# DL380P_r1_Fan_Control.net
KiCad netlist of a schematic drawn in EAGLE
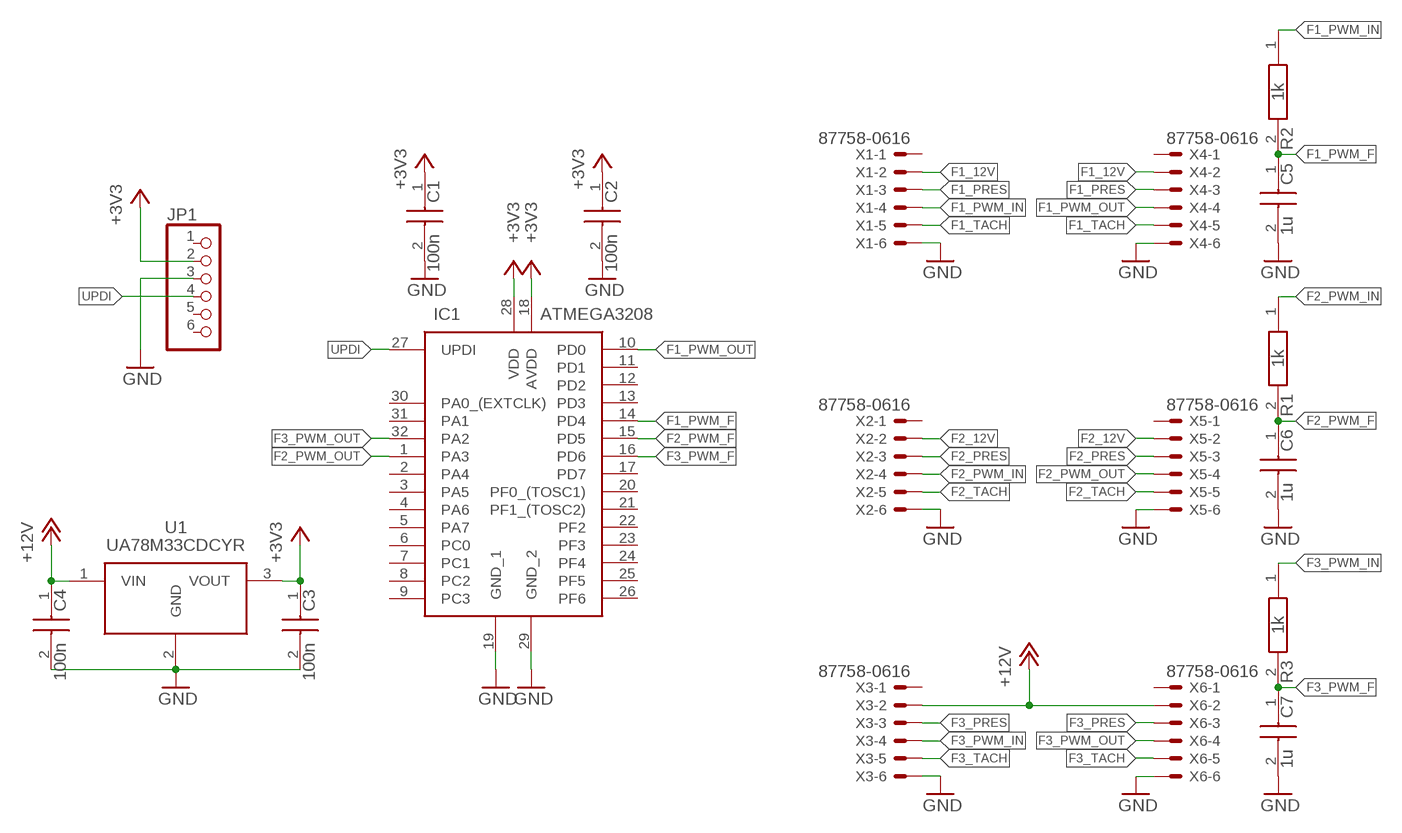
[diagram p0: schematic, sheet 1]

(export (version "E")
  (design (tool "Eeschema 10.0.6"))
  (components
    (comp (ref "C1")
      (value "100n")
      (footprint "eagle-import:CAPC1608X90N")
      (fields
        (field (name "MANUFACTURER_PART_NUMBER") "06033C104KAT2A")
        (field (name "MOUSER_PART_NUMBER") "581-06033C104KAT2A")
      )
      (libsource (lib "eagle-import") (part "_CAP_0603_100N_25V_10%_(X7R)"))
    )
    (comp (ref "C2")
      (value "100n")
      (footprint "eagle-import:CAPC1608X90N")
      (fields
        (field (name "MANUFACTURER_PART_NUMBER") "06033C104KAT2A")
        (field (name "MOUSER_PART_NUMBER") "581-06033C104KAT2A")
      )
      (libsource (lib "eagle-import") (part "_CAP_0603_100N_25V_10%_(X7R)"))
    )
    (comp (ref "C3")
      (value "100n")
      (footprint "eagle-import:CAPC1608X90N")
      (fields
        (field (name "MANUFACTURER_PART_NUMBER") "06033C104KAT2A")
        (field (name "MOUSER_PART_NUMBER") "581-06033C104KAT2A")
      )
      (libsource (lib "eagle-import") (part "_CAP_0603_100N_25V_10%_(X7R)"))
    )
    (comp (ref "C4")
      (value "100n")
      (footprint "eagle-import:CAPC1608X90N")
      (fields
        (field (name "MANUFACTURER_PART_NUMBER") "06033C104KAT2A")
        (field (name "MOUSER_PART_NUMBER") "581-06033C104KAT2A")
      )
      (libsource (lib "eagle-import") (part "_CAP_0603_100N_25V_10%_(X7R)"))
    )
    (comp (ref "C5")
      (value "1u")
      (footprint "eagle-import:CAPC1608X90N")
      (fields
        (field (name "MANUFACTURER_PART_NUMBER") "06033C105KAT2A")
        (field (name "MOUSER_PART_NUMBER") "581-06033C105KAT2A")
      )
      (libsource (lib "eagle-import") (part "_CAP_0603_1U_25V_10%_(X7R)"))
    )
    (comp (ref "C6")
      (value "1u")
      (footprint "eagle-import:CAPC1608X90N")
      (fields
        (field (name "MANUFACTURER_PART_NUMBER") "06033C105KAT2A")
        (field (name "MOUSER_PART_NUMBER") "581-06033C105KAT2A")
      )
      (libsource (lib "eagle-import") (part "_CAP_0603_1U_25V_10%_(X7R)"))
    )
    (comp (ref "C7")
      (value "1u")
      (footprint "eagle-import:CAPC1608X90N")
      (fields
        (field (name "MANUFACTURER_PART_NUMBER") "06033C105KAT2A")
        (field (name "MOUSER_PART_NUMBER") "581-06033C105KAT2A")
      )
      (libsource (lib "eagle-import") (part "_CAP_0603_1U_25V_10%_(X7R)"))
    )
    (comp (ref "IC1")
      (value "ATMEGA3208")
      (footprint "eagle-import:QFP80P900X900X120-32N")
      (fields
        (field (name "MANUFACTURER_PART_NUMBER") "ATMEGA3208-AFR")
        (field (name "MOUSER_PART_NUMBER") "579-ATMEGA3208AFR")
      )
      (libsource (lib "eagle-import") (part "_UC_ATMEGA3208-TQFP-32"))
    )
    (comp (ref "JP1")
      (value "PINHD-1X6LOCK")
      (footprint "eagle-import:1X06-BIGLOCK")
      (libsource (lib "eagle-import") (part "PINHD-1X6LOCK"))
    )
    (comp (ref "R1")
      (value "1k")
      (footprint "eagle-import:RESC1608X55N")
      (fields
        (field (name "MANUFACTURER_PART_NUMBER") "RK73H1JTTDD1001F")
        (field (name "MOUSER_PART_NUMBER") "660-RK73H1JTTDD1001F")
      )
      (libsource (lib "eagle-import") (part "_RES_0603_1K_1/10W_1%_(RK73H1JTTD)"))
    )
    (comp (ref "R2")
      (value "1k")
      (footprint "eagle-import:RESC1608X55N")
      (fields
        (field (name "MANUFACTURER_PART_NUMBER") "RK73H1JTTDD1001F")
        (field (name "MOUSER_PART_NUMBER") "660-RK73H1JTTDD1001F")
      )
      (libsource (lib "eagle-import") (part "_RES_0603_1K_1/10W_1%_(RK73H1JTTD)"))
    )
    (comp (ref "R3")
      (value "1k")
      (footprint "eagle-import:RESC1608X55N")
      (fields
        (field (name "MANUFACTURER_PART_NUMBER") "RK73H1JTTDD1001F")
        (field (name "MOUSER_PART_NUMBER") "660-RK73H1JTTDD1001F")
      )
      (libsource (lib "eagle-import") (part "_RES_0603_1K_1/10W_1%_(RK73H1JTTD)"))
    )
    (comp (ref "U1")
      (value "UA78M33CDCYR")
      (footprint "eagle-import:SOT230P700X180-4N")
      (fields (field (name "MOUSER_PART_NUMBER") "595-UA78M33CDCYR"))
      (libsource (lib "eagle-import") (part "_REG_3.3V_0.5A_SOT-223_(5.3-25V)_(UA78M33CDCYR)"))
    )
    (comp (ref "X1")
      (value "87758-0616")
      (footprint "eagle-import:87758-0616")
      (fields (field (name "MF") "MOLEX"))
      (libsource (lib "eagle-import") (part "87758-0616"))
    )
    (comp (ref "X2")
      (value "87758-0616")
      (footprint "eagle-import:87758-0616")
      (fields (field (name "MF") "MOLEX"))
      (libsource (lib "eagle-import") (part "87758-0616"))
    )
    (comp (ref "X3")
      (value "87758-0616")
      (footprint "eagle-import:87758-0616")
      (fields (field (name "MF") "MOLEX"))
      (libsource (lib "eagle-import") (part "87758-0616"))
    )
    (comp (ref "X4")
      (value "87758-0616")
      (footprint "eagle-import:87758-0616")
      (fields (field (name "MF") "MOLEX"))
      (libsource (lib "eagle-import") (part "87758-0616"))
    )
    (comp (ref "X5")
      (value "87758-0616")
      (footprint "eagle-import:87758-0616")
      (fields (field (name "MF") "MOLEX"))
      (libsource (lib "eagle-import") (part "87758-0616"))
    )
    (comp (ref "X6")
      (value "87758-0616")
      (footprint "eagle-import:87758-0616")
      (fields (field (name "MF") "MOLEX"))
      (libsource (lib "eagle-import") (part "87758-0616"))
    )
  )
  (nets
    (net (code "1") (name "+3V3") (class "Default")
      (node (ref "C1") (pin "1") (pinfunction "1_1") (pintype "bidirectional"))
      (node (ref "C2") (pin "1") (pinfunction "1_1") (pintype "bidirectional"))
      (node (ref "C3") (pin "1") (pinfunction "1_1") (pintype "bidirectional"))
      (node (ref "IC1") (pin "18") (pinfunction "AVDD_18") (pintype "bidirectional"))
      (node (ref "IC1") (pin "28") (pinfunction "VDD_28") (pintype "bidirectional"))
      (node (ref "JP1") (pin "2") (pinfunction "2_2") (pintype "passive"))
      (node (ref "U1") (pin "3") (pinfunction "VOUT_3") (pintype "bidirectional"))
    )
    (net (code "2") (name "+12V") (class "Default")
      (node (ref "C4") (pin "1") (pinfunction "1_1") (pintype "bidirectional"))
      (node (ref "U1") (pin "1") (pinfunction "VIN_1") (pintype "bidirectional"))
      (node (ref "X3") (pin "2") (pinfunction "S_2") (pintype "passive"))
      (node (ref "X6") (pin "2") (pinfunction "S_2") (pintype "passive"))
    )
    (net (code "3") (name "F1_12V") (class "Default")
      (node (ref "X1") (pin "2") (pinfunction "S_2") (pintype "passive"))
      (node (ref "X4") (pin "2") (pinfunction "S_2") (pintype "passive"))
    )
    (net (code "4") (name "F1_PRES") (class "Default")
      (node (ref "X1") (pin "3") (pinfunction "S_3") (pintype "passive"))
      (node (ref "X4") (pin "3") (pinfunction "S_3") (pintype "passive"))
    )
    (net (code "5") (name "F1_PWM_F") (class "Default")
      (node (ref "C5") (pin "1") (pinfunction "1_1") (pintype "bidirectional"))
      (node (ref "IC1") (pin "14") (pinfunction "PD4_14") (pintype "bidirectional"))
      (node (ref "R2") (pin "2") (pinfunction "2_2") (pintype "bidirectional"))
    )
    (net (code "6") (name "F1_PWM_IN") (class "Default")
      (node (ref "R2") (pin "1") (pinfunction "1_1") (pintype "bidirectional"))
      (node (ref "X1") (pin "4") (pinfunction "S_4") (pintype "passive"))
    )
    (net (code "7") (name "F1_PWM_OUT") (class "Default")
      (node (ref "IC1") (pin "10") (pinfunction "PD0_10") (pintype "bidirectional"))
      (node (ref "X4") (pin "4") (pinfunction "S_4") (pintype "passive"))
    )
    (net (code "8") (name "F1_TACH") (class "Default")
      (node (ref "X1") (pin "5") (pinfunction "S_5") (pintype "passive"))
      (node (ref "X4") (pin "5") (pinfunction "S_5") (pintype "passive"))
    )
    (net (code "9") (name "F2_12V") (class "Default")
      (node (ref "X2") (pin "2") (pinfunction "S_2") (pintype "passive"))
      (node (ref "X5") (pin "2") (pinfunction "S_2") (pintype "passive"))
    )
    (net (code "10") (name "F2_PRES") (class "Default")
      (node (ref "X2") (pin "3") (pinfunction "S_3") (pintype "passive"))
      (node (ref "X5") (pin "3") (pinfunction "S_3") (pintype "passive"))
    )
    (net (code "11") (name "F2_PWM_F") (class "Default")
      (node (ref "C6") (pin "1") (pinfunction "1_1") (pintype "bidirectional"))
      (node (ref "IC1") (pin "15") (pinfunction "PD5_15") (pintype "bidirectional"))
      (node (ref "R1") (pin "2") (pinfunction "2_2") (pintype "bidirectional"))
    )
    (net (code "12") (name "F2_PWM_IN") (class "Default")
      (node (ref "R1") (pin "1") (pinfunction "1_1") (pintype "bidirectional"))
      (node (ref "X2") (pin "4") (pinfunction "S_4") (pintype "passive"))
    )
    (net (code "13") (name "F2_PWM_OUT") (class "Default")
      (node (ref "IC1") (pin "1") (pinfunction "PA3_1") (pintype "bidirectional"))
      (node (ref "X5") (pin "4") (pinfunction "S_4") (pintype "passive"))
    )
    (net (code "14") (name "F2_TACH") (class "Default")
      (node (ref "X2") (pin "5") (pinfunction "S_5") (pintype "passive"))
      (node (ref "X5") (pin "5") (pinfunction "S_5") (pintype "passive"))
    )
    (net (code "15") (name "F3_PRES") (class "Default")
      (node (ref "X3") (pin "3") (pinfunction "S_3") (pintype "passive"))
      (node (ref "X6") (pin "3") (pinfunction "S_3") (pintype "passive"))
    )
    (net (code "16") (name "F3_PWM_F") (class "Default")
      (node (ref "C7") (pin "1") (pinfunction "1_1") (pintype "bidirectional"))
      (node (ref "IC1") (pin "16") (pinfunction "PD6_16") (pintype "bidirectional"))
      (node (ref "R3") (pin "2") (pinfunction "2_2") (pintype "bidirectional"))
    )
    (net (code "17") (name "F3_PWM_IN") (class "Default")
      (node (ref "R3") (pin "1") (pinfunction "1_1") (pintype "bidirectional"))
      (node (ref "X3") (pin "4") (pinfunction "S_4") (pintype "passive"))
    )
    (net (code "18") (name "F3_PWM_OUT") (class "Default")
      (node (ref "IC1") (pin "32") (pinfunction "PA2_32") (pintype "bidirectional"))
      (node (ref "X6") (pin "4") (pinfunction "S_4") (pintype "passive"))
    )
    (net (code "19") (name "F3_TACH") (class "Default")
      (node (ref "X3") (pin "5") (pinfunction "S_5") (pintype "passive"))
      (node (ref "X6") (pin "5") (pinfunction "S_5") (pintype "passive"))
    )
    (net (code "20") (name "GND") (class "Default")
      (node (ref "C1") (pin "2") (pinfunction "2_2") (pintype "bidirectional"))
      (node (ref "C2") (pin "2") (pinfunction "2_2") (pintype "bidirectional"))
      (node (ref "C3") (pin "2") (pinfunction "2_2") (pintype "bidirectional"))
      (node (ref "C4") (pin "2") (pinfunction "2_2") (pintype "bidirectional"))
      (node (ref "C5") (pin "2") (pinfunction "2_2") (pintype "bidirectional"))
      (node (ref "C6") (pin "2") (pinfunction "2_2") (pintype "bidirectional"))
      (node (ref "C7") (pin "2") (pinfunction "2_2") (pintype "bidirectional"))
      (node (ref "IC1") (pin "19") (pinfunction "GND_1_19") (pintype "bidirectional"))
      (node (ref "IC1") (pin "29") (pinfunction "GND_2_29") (pintype "bidirectional"))
      (node (ref "JP1") (pin "3") (pinfunction "3_3") (pintype "passive"))
      (node (ref "U1") (pin "2") (pinfunction "GND_2") (pintype "bidirectional"))
      (node (ref "U1") (pin "4") (pinfunction "GND_1_4") (pintype "bidirectional"))
      (node (ref "X1") (pin "6") (pinfunction "S_6") (pintype "passive"))
      (node (ref "X2") (pin "6") (pinfunction "S_6") (pintype "passive"))
      (node (ref "X3") (pin "6") (pinfunction "S_6") (pintype "passive"))
      (node (ref "X4") (pin "6") (pinfunction "S_6") (pintype "passive"))
      (node (ref "X5") (pin "6") (pinfunction "S_6") (pintype "passive"))
      (node (ref "X6") (pin "6") (pinfunction "S_6") (pintype "passive"))
    )
    (net (code "21") (name "UPDI") (class "Default")
      (node (ref "IC1") (pin "27") (pinfunction "UPDI_27") (pintype "bidirectional"))
      (node (ref "JP1") (pin "4") (pinfunction "4_4") (pintype "passive"))
    )
    (net (code "22") (name "unconnected-(IC1-PA0_(EXTCLK)-Pad30)") (class "Default")
      (node (ref "IC1") (pin "30") (pinfunction "PA0_(EXTCLK)_30") (pintype "bidirectional"))
    )
    (net (code "23") (name "unconnected-(IC1-PA1-Pad31)") (class "Default")
      (node (ref "IC1") (pin "31") (pinfunction "PA1_31") (pintype "bidirectional"))
    )
    (net (code "24") (name "unconnected-(IC1-PA4-Pad2)") (class "Default")
      (node (ref "IC1") (pin "2") (pinfunction "PA4_2") (pintype "bidirectional"))
    )
    (net (code "25") (name "unconnected-(IC1-PA5-Pad3)") (class "Default")
      (node (ref "IC1") (pin "3") (pinfunction "PA5_3") (pintype "bidirectional"))
    )
    (net (code "26") (name "unconnected-(IC1-PA6-Pad4)") (class "Default")
      (node (ref "IC1") (pin "4") (pinfunction "PA6_4") (pintype "bidirectional"))
    )
    (net (code "27") (name "unconnected-(IC1-PA7-Pad5)") (class "Default")
      (node (ref "IC1") (pin "5") (pinfunction "PA7_5") (pintype "bidirectional"))
    )
    (net (code "28") (name "unconnected-(IC1-PC0-Pad6)") (class "Default")
      (node (ref "IC1") (pin "6") (pinfunction "PC0_6") (pintype "bidirectional"))
    )
    (net (code "29") (name "unconnected-(IC1-PC1-Pad7)") (class "Default")
      (node (ref "IC1") (pin "7") (pinfunction "PC1_7") (pintype "bidirectional"))
    )
    (net (code "30") (name "unconnected-(IC1-PC2-Pad8)") (class "Default")
      (node (ref "IC1") (pin "8") (pinfunction "PC2_8") (pintype "bidirectional"))
    )
    (net (code "31") (name "unconnected-(IC1-PC3-Pad9)") (class "Default")
      (node (ref "IC1") (pin "9") (pinfunction "PC3_9") (pintype "bidirectional"))
    )
    (net (code "32") (name "unconnected-(IC1-PD1-Pad11)") (class "Default")
      (node (ref "IC1") (pin "11") (pinfunction "PD1_11") (pintype "bidirectional"))
    )
    (net (code "33") (name "unconnected-(IC1-PD2-Pad12)") (class "Default")
      (node (ref "IC1") (pin "12") (pinfunction "PD2_12") (pintype "bidirectional"))
    )
    (net (code "34") (name "unconnected-(IC1-PD3-Pad13)") (class "Default")
      (node (ref "IC1") (pin "13") (pinfunction "PD3_13") (pintype "bidirectional"))
    )
    (net (code "35") (name "unconnected-(IC1-PD7-Pad17)") (class "Default")
      (node (ref "IC1") (pin "17") (pinfunction "PD7_17") (pintype "bidirectional"))
    )
    (net (code "36") (name "unconnected-(IC1-PF0_(TOSC1)-Pad20)") (class "Default")
      (node (ref "IC1") (pin "20") (pinfunction "PF0_(TOSC1)_20") (pintype "bidirectional"))
    )
    (net (code "37") (name "unconnected-(IC1-PF1_(TOSC2)-Pad21)") (class "Default")
      (node (ref "IC1") (pin "21") (pinfunction "PF1_(TOSC2)_21") (pintype "bidirectional"))
    )
    (net (code "38") (name "unconnected-(IC1-PF2-Pad22)") (class "Default")
      (node (ref "IC1") (pin "22") (pinfunction "PF2_22") (pintype "bidirectional"))
    )
    (net (code "39") (name "unconnected-(IC1-PF3-Pad23)") (class "Default")
      (node (ref "IC1") (pin "23") (pinfunction "PF3_23") (pintype "bidirectional"))
    )
    (net (code "40") (name "unconnected-(IC1-PF4-Pad24)") (class "Default")
      (node (ref "IC1") (pin "24") (pinfunction "PF4_24") (pintype "bidirectional"))
    )
    (net (code "41") (name "unconnected-(IC1-PF5-Pad25)") (class "Default")
      (node (ref "IC1") (pin "25") (pinfunction "PF5_25") (pintype "bidirectional"))
    )
    (net (code "42") (name "unconnected-(IC1-PF6-Pad26)") (class "Default")
      (node (ref "IC1") (pin "26") (pinfunction "PF6_26") (pintype "bidirectional"))
    )
    (net (code "43") (name "unconnected-(JP1-Pad1)") (class "Default")
      (node (ref "JP1") (pin "1") (pinfunction "1_1") (pintype "passive"))
    )
    (net (code "44") (name "unconnected-(JP1-Pad5)") (class "Default")
      (node (ref "JP1") (pin "5") (pinfunction "5_5") (pintype "passive"))
    )
    (net (code "45") (name "unconnected-(JP1-Pad6)") (class "Default")
      (node (ref "JP1") (pin "6") (pinfunction "6_6") (pintype "passive"))
    )
    (net (code "46") (name "unconnected-(X1A-S-Pad1)") (class "Default")
      (node (ref "X1") (pin "1") (pinfunction "S_1") (pintype "passive"))
    )
    (net (code "47") (name "unconnected-(X2A-S-Pad1)") (class "Default")
      (node (ref "X2") (pin "1") (pinfunction "S_1") (pintype "passive"))
    )
    (net (code "48") (name "unconnected-(X3A-S-Pad1)") (class "Default")
      (node (ref "X3") (pin "1") (pinfunction "S_1") (pintype "passive"))
    )
    (net (code "49") (name "unconnected-(X4A-S-Pad1)") (class "Default")
      (node (ref "X4") (pin "1") (pinfunction "S_1") (pintype "passive"))
    )
    (net (code "50") (name "unconnected-(X5A-S-Pad1)") (class "Default")
      (node (ref "X5") (pin "1") (pinfunction "S_1") (pintype "passive"))
    )
    (net (code "51") (name "unconnected-(X6A-S-Pad1)") (class "Default")
      (node (ref "X6") (pin "1") (pinfunction "S_1") (pintype "passive"))
    )
  )
)
